# JTAG_ALTIUM_HOST.net
KiCad netlist of a schematic drawn in Altium Designer
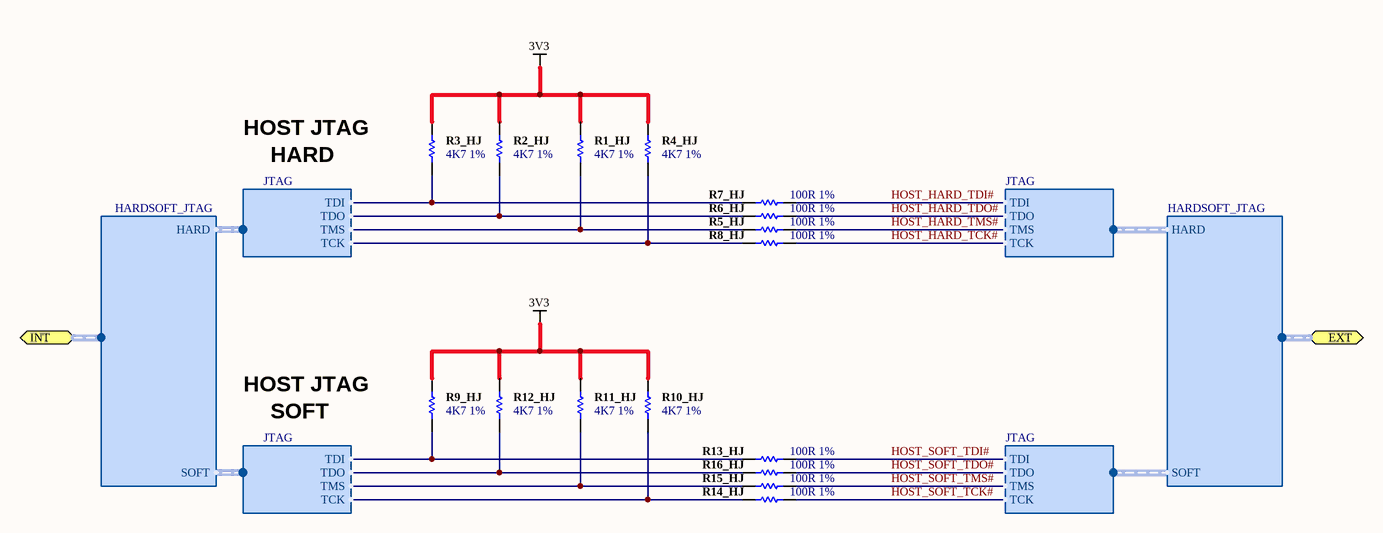
[diagram p0: JTAG_ALTIUM_HOST.SchDoc]

(export (version "E")
  (design (tool "Eeschema 10.0.6"))
  (components
    (comp (ref "R1_HJ")
      (value "4K7 1%")
      (footprint "RESC1005-STAR")
      (description "Resistor, 4K7 1% 0402 (1005)")
      (fields (field (name "TOLERANCE") "1 %"))
      (libsource (lib "AltiumDesignLibrary") (part "RES"))
    )
    (comp (ref "R2_HJ")
      (value "4K7 1%")
      (footprint "RESC1005-STAR")
      (description "Resistor, 4K7 1% 0402 (1005)")
      (fields (field (name "TOLERANCE") "1 %"))
      (libsource (lib "AltiumDesignLibrary") (part "RES"))
    )
    (comp (ref "R3_HJ")
      (value "4K7 1%")
      (footprint "RESC1005-STAR")
      (description "Resistor, 4K7 1% 0402 (1005)")
      (fields (field (name "TOLERANCE") "1 %"))
      (libsource (lib "AltiumDesignLibrary") (part "RES"))
    )
    (comp (ref "R4_HJ")
      (value "4K7 1%")
      (footprint "RESC1005-STAR")
      (description "Resistor, 4K7 1% 0402 (1005)")
      (fields (field (name "TOLERANCE") "1 %"))
      (libsource (lib "AltiumDesignLibrary") (part "RES"))
    )
    (comp (ref "R5_HJ")
      (value "100R 1%")
      (footprint "RESC1005-STAR")
      (description "Resistor, 100R 1% 0402 (1005)")
      (fields (field (name "TOLERANCE") "1 %"))
      (libsource (lib "AltiumDesignLibrary") (part "RES"))
    )
    (comp (ref "R6_HJ")
      (value "100R 1%")
      (footprint "RESC1005-STAR")
      (description "Resistor, 100R 1% 0402 (1005)")
      (fields (field (name "TOLERANCE") "1 %"))
      (libsource (lib "AltiumDesignLibrary") (part "RES"))
    )
    (comp (ref "R7_HJ")
      (value "100R 1%")
      (footprint "RESC1005-STAR")
      (description "Resistor, 100R 1% 0402 (1005)")
      (fields (field (name "TOLERANCE") "1 %"))
      (libsource (lib "AltiumDesignLibrary") (part "RES"))
    )
    (comp (ref "R8_HJ")
      (value "100R 1%")
      (footprint "RESC1005-STAR")
      (description "Resistor, 100R 1% 0402 (1005)")
      (fields (field (name "TOLERANCE") "1 %"))
      (libsource (lib "AltiumDesignLibrary") (part "RES"))
    )
    (comp (ref "R9_HJ")
      (value "4K7 1%")
      (footprint "RESC1005-STAR")
      (description "Resistor, 4K7 1% 0402 (1005)")
      (fields (field (name "TOLERANCE") "1 %"))
      (libsource (lib "AltiumDesignLibrary") (part "RES"))
    )
    (comp (ref "R10_HJ")
      (value "4K7 1%")
      (footprint "RESC1005-STAR")
      (description "Resistor, 4K7 1% 0402 (1005)")
      (fields (field (name "TOLERANCE") "1 %"))
      (libsource (lib "AltiumDesignLibrary") (part "RES"))
    )
    (comp (ref "R11_HJ")
      (value "4K7 1%")
      (footprint "RESC1005-STAR")
      (description "Resistor, 4K7 1% 0402 (1005)")
      (fields (field (name "TOLERANCE") "1 %"))
      (libsource (lib "AltiumDesignLibrary") (part "RES"))
    )
    (comp (ref "R12_HJ")
      (value "4K7 1%")
      (footprint "RESC1005-STAR")
      (description "Resistor, 4K7 1% 0402 (1005)")
      (fields (field (name "TOLERANCE") "1 %"))
      (libsource (lib "AltiumDesignLibrary") (part "RES"))
    )
    (comp (ref "R13_HJ")
      (value "100R 1%")
      (footprint "RESC1005-STAR")
      (description "Resistor, 100R 1% 0402 (1005)")
      (fields (field (name "TOLERANCE") "1 %"))
      (libsource (lib "AltiumDesignLibrary") (part "RES"))
    )
    (comp (ref "R14_HJ")
      (value "100R 1%")
      (footprint "RESC1005-STAR")
      (description "Resistor, 100R 1% 0402 (1005)")
      (fields (field (name "TOLERANCE") "1 %"))
      (libsource (lib "AltiumDesignLibrary") (part "RES"))
    )
    (comp (ref "R15_HJ")
      (value "100R 1%")
      (footprint "RESC1005-STAR")
      (description "Resistor, 100R 1% 0402 (1005)")
      (fields (field (name "TOLERANCE") "1 %"))
      (libsource (lib "AltiumDesignLibrary") (part "RES"))
    )
    (comp (ref "R16_HJ")
      (value "100R 1%")
      (footprint "RESC1005-STAR")
      (description "Resistor, 100R 1% 0402 (1005)")
      (fields (field (name "TOLERANCE") "1 %"))
      (libsource (lib "AltiumDesignLibrary") (part "RES"))
    )
  )
  (nets
    (net (code "4") (name "/HOST_HARD_TCK#") (class "Default")
      (node (ref "R8_HJ") (pin "2") (pinfunction "2_2") (pintype "passive"))
    )
    (net (code "5") (name "/HOST_HARD_TDI#") (class "Default")
      (node (ref "R7_HJ") (pin "2") (pinfunction "2_2") (pintype "passive"))
    )
    (net (code "6") (name "/HOST_HARD_TDO#") (class "Default")
      (node (ref "R6_HJ") (pin "2") (pinfunction "2_2") (pintype "passive"))
    )
    (net (code "7") (name "/HOST_HARD_TMS#") (class "Default")
      (node (ref "R5_HJ") (pin "2") (pinfunction "2_2") (pintype "passive"))
    )
    (net (code "8") (name "/HOST_SOFT_TCK#") (class "Default")
      (node (ref "R14_HJ") (pin "2") (pinfunction "2_2") (pintype "passive"))
    )
    (net (code "9") (name "/HOST_SOFT_TDI#") (class "Default")
      (node (ref "R13_HJ") (pin "2") (pinfunction "2_2") (pintype "passive"))
    )
    (net (code "10") (name "/HOST_SOFT_TDO#") (class "Default")
      (node (ref "R16_HJ") (pin "2") (pinfunction "2_2") (pintype "passive"))
    )
    (net (code "11") (name "/HOST_SOFT_TMS#") (class "Default")
      (node (ref "R15_HJ") (pin "2") (pinfunction "2_2") (pintype "passive"))
    )
    (net (code "15") (name "3V3") (class "Default")
      (node (ref "R10_HJ") (pin "2") (pinfunction "2_2") (pintype "passive"))
      (node (ref "R11_HJ") (pin "2") (pinfunction "2_2") (pintype "passive"))
      (node (ref "R12_HJ") (pin "2") (pinfunction "2_2") (pintype "passive"))
      (node (ref "R1_HJ") (pin "2") (pinfunction "2_2") (pintype "passive"))
      (node (ref "R2_HJ") (pin "2") (pinfunction "2_2") (pintype "passive"))
      (node (ref "R3_HJ") (pin "2") (pinfunction "2_2") (pintype "passive"))
      (node (ref "R4_HJ") (pin "2") (pinfunction "2_2") (pintype "passive"))
      (node (ref "R9_HJ") (pin "2") (pinfunction "2_2") (pintype "passive"))
    )
    (net (code "16") (name "Net-(R1_HJ-Pad1)") (class "Default")
      (node (ref "R1_HJ") (pin "1") (pinfunction "1_1") (pintype "passive"))
      (node (ref "R5_HJ") (pin "1") (pinfunction "1_1") (pintype "passive"))
    )
    (net (code "17") (name "Net-(R2_HJ-Pad1)") (class "Default")
      (node (ref "R2_HJ") (pin "1") (pinfunction "1_1") (pintype "passive"))
      (node (ref "R6_HJ") (pin "1") (pinfunction "1_1") (pintype "passive"))
    )
    (net (code "18") (name "Net-(R3_HJ-Pad1)") (class "Default")
      (node (ref "R3_HJ") (pin "1") (pinfunction "1_1") (pintype "passive"))
      (node (ref "R7_HJ") (pin "1") (pinfunction "1_1") (pintype "passive"))
    )
    (net (code "19") (name "Net-(R4_HJ-Pad1)") (class "Default")
      (node (ref "R4_HJ") (pin "1") (pinfunction "1_1") (pintype "passive"))
      (node (ref "R8_HJ") (pin "1") (pinfunction "1_1") (pintype "passive"))
    )
    (net (code "20") (name "Net-(R10_HJ-Pad1)") (class "Default")
      (node (ref "R10_HJ") (pin "1") (pinfunction "1_1") (pintype "passive"))
      (node (ref "R14_HJ") (pin "1") (pinfunction "1_1") (pintype "passive"))
    )
    (net (code "21") (name "Net-(R11_HJ-Pad1)") (class "Default")
      (node (ref "R11_HJ") (pin "1") (pinfunction "1_1") (pintype "passive"))
      (node (ref "R15_HJ") (pin "1") (pinfunction "1_1") (pintype "passive"))
    )
    (net (code "22") (name "Net-(R12_HJ-Pad1)") (class "Default")
      (node (ref "R12_HJ") (pin "1") (pinfunction "1_1") (pintype "passive"))
      (node (ref "R16_HJ") (pin "1") (pinfunction "1_1") (pintype "passive"))
    )
    (net (code "23") (name "Net-(R13_HJ-Pad1)") (class "Default")
      (node (ref "R13_HJ") (pin "1") (pinfunction "1_1") (pintype "passive"))
      (node (ref "R9_HJ") (pin "1") (pinfunction "1_1") (pintype "passive"))
    )
  )
)
